# ReadyUNO_SMD.net
KiCad netlist of a schematic drawn in EAGLE
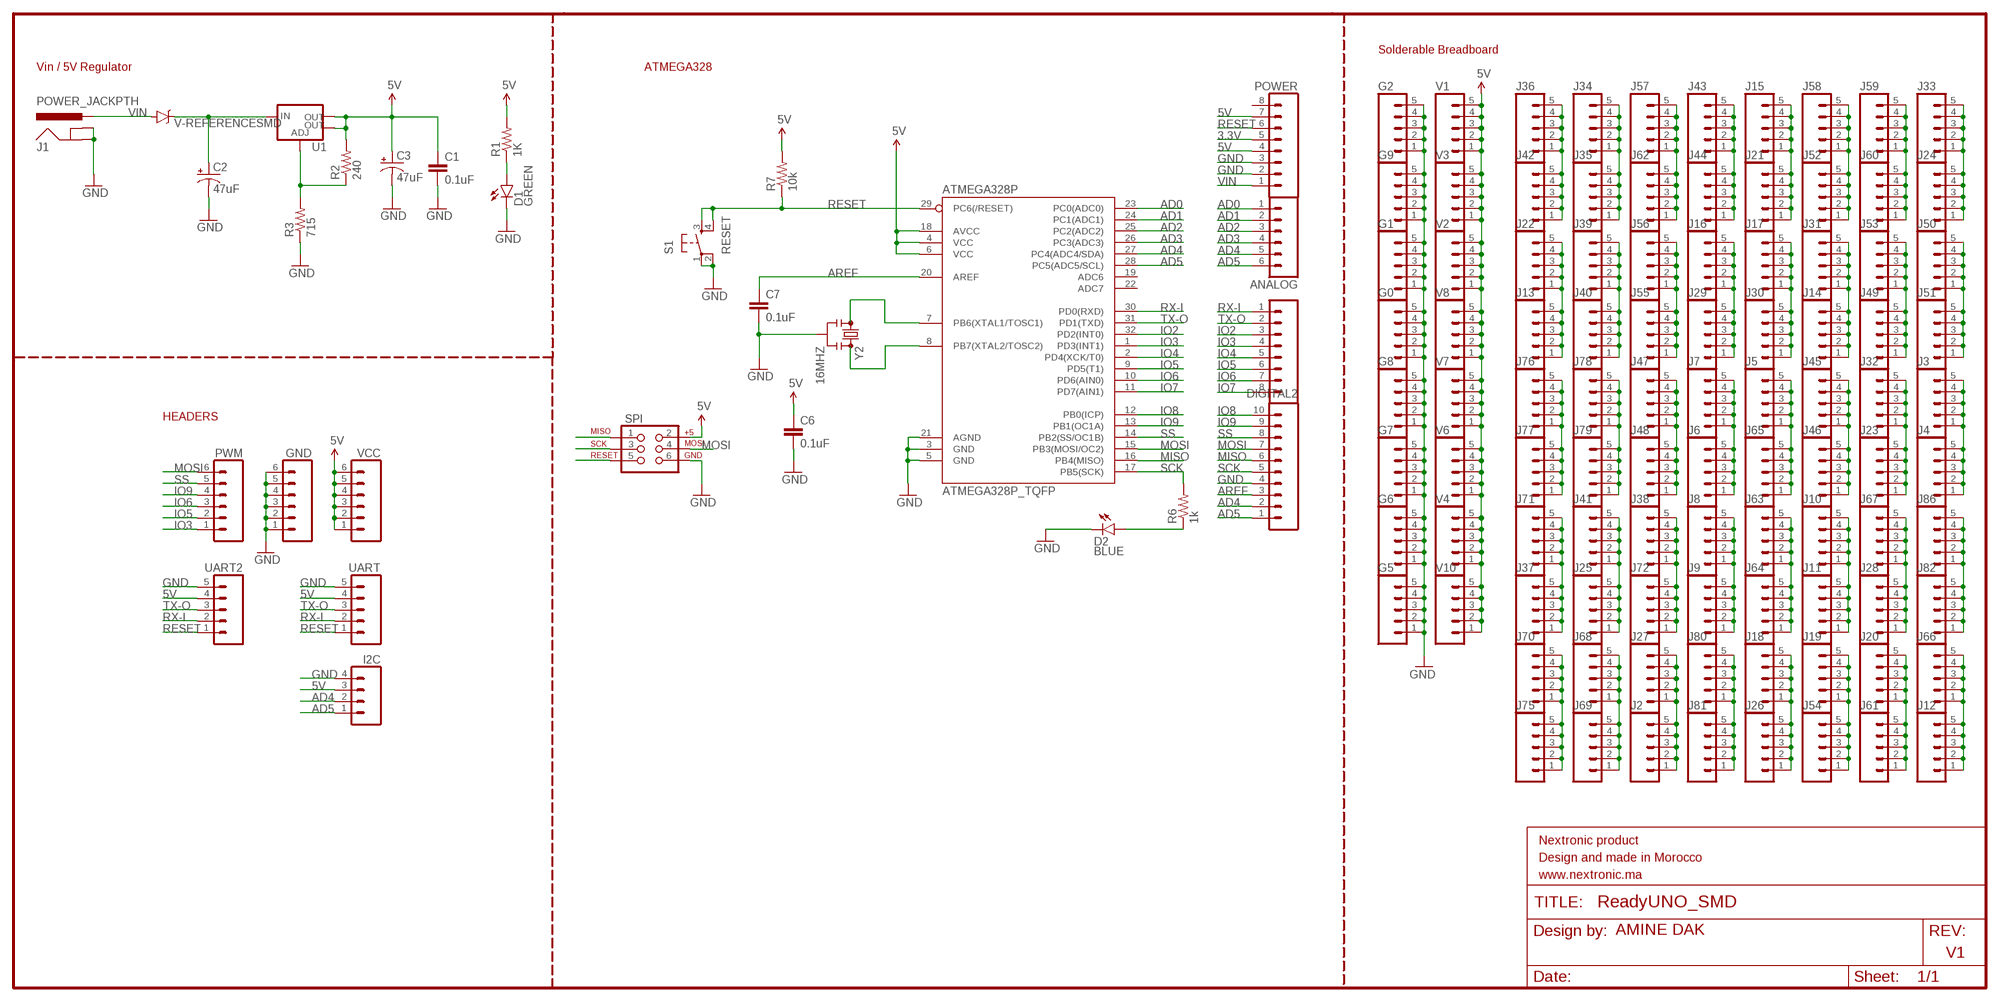
[diagram p0: schematic, sheet 1]

(export (version "E")
  (design (tool "Eeschema 10.0.6"))
  (components
    (comp (ref "ANALOG")
      (value "M06SILK_FEMALE_PTH")
      (footprint "eagle-import:1X06")
      (libsource (lib "eagle-import") (part "M06SILK_FEMALE_PTH"))
    )
    (comp (ref "ATMEGA328P")
      (value "ATMEGA328P_TQFP")
      (footprint "eagle-import:TQFP32-08")
      (libsource (lib "eagle-import") (part "ATMEGA328P_TQFP"))
    )
    (comp (ref "C1")
      (value "0.1uF")
      (footprint "eagle-import:0603-CAP")
      (libsource (lib "eagle-import") (part "CAP0603-CAP"))
    )
    (comp (ref "C2")
      (value "47uF")
      (footprint "eagle-import:PANASONIC_C")
      (libsource (lib "eagle-import") (part "CAP_POLC"))
    )
    (comp (ref "C3")
      (value "47uF")
      (footprint "eagle-import:PANASONIC_C")
      (libsource (lib "eagle-import") (part "CAP_POLC"))
    )
    (comp (ref "C6")
      (value "0.1uF")
      (footprint "eagle-import:0603-CAP")
      (libsource (lib "eagle-import") (part "CAP0603-CAP"))
    )
    (comp (ref "C7")
      (value "0.1uF")
      (footprint "eagle-import:0603-CAP")
      (libsource (lib "eagle-import") (part "CAP0603-CAP"))
    )
    (comp (ref "D1")
      (value "GREEN")
      (footprint "eagle-import:LED-1206")
      (libsource (lib "eagle-import") (part "LED-GREEN1206"))
    )
    (comp (ref "D2")
      (value "BLUE")
      (footprint "eagle-import:LED-1206")
      (libsource (lib "eagle-import") (part "LED-BLUE1206"))
    )
    (comp (ref "DIGITAL")
      (value "M08SILK_FEMALE_PTH")
      (footprint "eagle-import:1X08")
      (libsource (lib "eagle-import") (part "M08SILK_FEMALE_PTH"))
    )
    (comp (ref "DIGITAL2")
      (value "M10SILK_FEMALE_PTH")
      (footprint "eagle-import:1X10")
      (libsource (lib "eagle-import") (part "M10SILK_FEMALE_PTH"))
    )
    (comp (ref "FRAME1")
      (value "FRAME-LETTER")
      (footprint "eagle-import:CREATIVE_COMMONS")
      (libsource (lib "eagle-import") (part "FRAME-LETTER"))
    )
    (comp (ref "G0")
      (value "M05PTH")
      (footprint "eagle-import:1X05")
      (libsource (lib "eagle-import") (part "M05PTH"))
    )
    (comp (ref "G1")
      (value "M05PTH")
      (footprint "eagle-import:1X05")
      (libsource (lib "eagle-import") (part "M05PTH"))
    )
    (comp (ref "G2")
      (value "M05PTH")
      (footprint "eagle-import:1X05")
      (libsource (lib "eagle-import") (part "M05PTH"))
    )
    (comp (ref "G5")
      (value "M05PTH")
      (footprint "eagle-import:1X05")
      (libsource (lib "eagle-import") (part "M05PTH"))
    )
    (comp (ref "G6")
      (value "M05PTH")
      (footprint "eagle-import:1X05")
      (libsource (lib "eagle-import") (part "M05PTH"))
    )
    (comp (ref "G7")
      (value "M05PTH")
      (footprint "eagle-import:1X05")
      (libsource (lib "eagle-import") (part "M05PTH"))
    )
    (comp (ref "G8")
      (value "M05PTH")
      (footprint "eagle-import:1X05")
      (libsource (lib "eagle-import") (part "M05PTH"))
    )
    (comp (ref "G9")
      (value "M05PTH")
      (footprint "eagle-import:1X05")
      (libsource (lib "eagle-import") (part "M05PTH"))
    )
    (comp (ref "GND")
      (value "M06SILK_FEMALE_PTH")
      (footprint "eagle-import:1X06")
      (libsource (lib "eagle-import") (part "M06SILK_FEMALE_PTH"))
    )
    (comp (ref "I2C")
      (value "M04PTH")
      (footprint "eagle-import:1X04")
      (libsource (lib "eagle-import") (part "M04PTH"))
    )
    (comp (ref "J1")
      (value "POWER_JACKPTH")
      (footprint "eagle-import:POWER_JACK_PTH")
      (libsource (lib "eagle-import") (part "POWER_JACKPTH"))
    )
    (comp (ref "J2")
      (value "M05PTH")
      (footprint "eagle-import:1X05")
      (libsource (lib "eagle-import") (part "M05PTH"))
    )
    (comp (ref "J3")
      (value "M05PTH")
      (footprint "eagle-import:1X05")
      (libsource (lib "eagle-import") (part "M05PTH"))
    )
    (comp (ref "J4")
      (value "M05PTH")
      (footprint "eagle-import:1X05")
      (libsource (lib "eagle-import") (part "M05PTH"))
    )
    (comp (ref "J5")
      (value "M05PTH")
      (footprint "eagle-import:1X05")
      (libsource (lib "eagle-import") (part "M05PTH"))
    )
    (comp (ref "J6")
      (value "M05PTH")
      (footprint "eagle-import:1X05")
      (libsource (lib "eagle-import") (part "M05PTH"))
    )
    (comp (ref "J7")
      (value "M05PTH")
      (footprint "eagle-import:1X05")
      (libsource (lib "eagle-import") (part "M05PTH"))
    )
    (comp (ref "J8")
      (value "M05PTH")
      (footprint "eagle-import:1X05")
      (libsource (lib "eagle-import") (part "M05PTH"))
    )
    (comp (ref "J9")
      (value "M05PTH")
      (footprint "eagle-import:1X05")
      (libsource (lib "eagle-import") (part "M05PTH"))
    )
    (comp (ref "J10")
      (value "M05PTH")
      (footprint "eagle-import:1X05")
      (libsource (lib "eagle-import") (part "M05PTH"))
    )
    (comp (ref "J11")
      (value "M05PTH")
      (footprint "eagle-import:1X05")
      (libsource (lib "eagle-import") (part "M05PTH"))
    )
    (comp (ref "J12")
      (value "M05PTH")
      (footprint "eagle-import:1X05")
      (libsource (lib "eagle-import") (part "M05PTH"))
    )
    (comp (ref "J13")
      (value "M05PTH")
      (footprint "eagle-import:1X05")
      (libsource (lib "eagle-import") (part "M05PTH"))
    )
    (comp (ref "J14")
      (value "M05PTH")
      (footprint "eagle-import:1X05")
      (libsource (lib "eagle-import") (part "M05PTH"))
    )
    (comp (ref "J15")
      (value "M05PTH")
      (footprint "eagle-import:1X05")
      (libsource (lib "eagle-import") (part "M05PTH"))
    )
    (comp (ref "J16")
      (value "M05PTH")
      (footprint "eagle-import:1X05")
      (libsource (lib "eagle-import") (part "M05PTH"))
    )
    (comp (ref "J17")
      (value "M05PTH")
      (footprint "eagle-import:1X05")
      (libsource (lib "eagle-import") (part "M05PTH"))
    )
    (comp (ref "J18")
      (value "M05PTH")
      (footprint "eagle-import:1X05")
      (libsource (lib "eagle-import") (part "M05PTH"))
    )
    (comp (ref "J19")
      (value "M05PTH")
      (footprint "eagle-import:1X05")
      (libsource (lib "eagle-import") (part "M05PTH"))
    )
    (comp (ref "J20")
      (value "M05PTH")
      (footprint "eagle-import:1X05")
      (libsource (lib "eagle-import") (part "M05PTH"))
    )
    (comp (ref "J21")
      (value "M05PTH")
      (footprint "eagle-import:1X05")
      (libsource (lib "eagle-import") (part "M05PTH"))
    )
    (comp (ref "J22")
      (value "M05PTH")
      (footprint "eagle-import:1X05")
      (libsource (lib "eagle-import") (part "M05PTH"))
    )
    (comp (ref "J23")
      (value "M05PTH")
      (footprint "eagle-import:1X05")
      (libsource (lib "eagle-import") (part "M05PTH"))
    )
    (comp (ref "J24")
      (value "M05PTH")
      (footprint "eagle-import:1X05")
      (libsource (lib "eagle-import") (part "M05PTH"))
    )
    (comp (ref "J25")
      (value "M05PTH")
      (footprint "eagle-import:1X05")
      (libsource (lib "eagle-import") (part "M05PTH"))
    )
    (comp (ref "J26")
      (value "M05PTH")
      (footprint "eagle-import:1X05")
      (libsource (lib "eagle-import") (part "M05PTH"))
    )
    (comp (ref "J27")
      (value "M05PTH")
      (footprint "eagle-import:1X05")
      (libsource (lib "eagle-import") (part "M05PTH"))
    )
    (comp (ref "J28")
      (value "M05PTH")
      (footprint "eagle-import:1X05")
      (libsource (lib "eagle-import") (part "M05PTH"))
    )
    (comp (ref "J29")
      (value "M05PTH")
      (footprint "eagle-import:1X05")
      (libsource (lib "eagle-import") (part "M05PTH"))
    )
    (comp (ref "J30")
      (value "M05PTH")
      (footprint "eagle-import:1X05")
      (libsource (lib "eagle-import") (part "M05PTH"))
    )
    (comp (ref "J31")
      (value "M05PTH")
      (footprint "eagle-import:1X05")
      (libsource (lib "eagle-import") (part "M05PTH"))
    )
    (comp (ref "J32")
      (value "M05PTH")
      (footprint "eagle-import:1X05")
      (libsource (lib "eagle-import") (part "M05PTH"))
    )
    (comp (ref "J33")
      (value "M05PTH")
      (footprint "eagle-import:1X05")
      (libsource (lib "eagle-import") (part "M05PTH"))
    )
    (comp (ref "J34")
      (value "M05PTH")
      (footprint "eagle-import:1X05")
      (libsource (lib "eagle-import") (part "M05PTH"))
    )
    (comp (ref "J35")
      (value "M05PTH")
      (footprint "eagle-import:1X05")
      (libsource (lib "eagle-import") (part "M05PTH"))
    )
    (comp (ref "J36")
      (value "M05PTH")
      (footprint "eagle-import:1X05")
      (libsource (lib "eagle-import") (part "M05PTH"))
    )
    (comp (ref "J37")
      (value "M05PTH")
      (footprint "eagle-import:1X05")
      (libsource (lib "eagle-import") (part "M05PTH"))
    )
    (comp (ref "J38")
      (value "M05PTH")
      (footprint "eagle-import:1X05")
      (libsource (lib "eagle-import") (part "M05PTH"))
    )
    (comp (ref "J39")
      (value "M05PTH")
      (footprint "eagle-import:1X05")
      (libsource (lib "eagle-import") (part "M05PTH"))
    )
    (comp (ref "J40")
      (value "M05PTH")
      (footprint "eagle-import:1X05")
      (libsource (lib "eagle-import") (part "M05PTH"))
    )
    (comp (ref "J41")
      (value "M05PTH")
      (footprint "eagle-import:1X05")
      (libsource (lib "eagle-import") (part "M05PTH"))
    )
    (comp (ref "J42")
      (value "M05PTH")
      (footprint "eagle-import:1X05")
      (libsource (lib "eagle-import") (part "M05PTH"))
    )
    (comp (ref "J43")
      (value "M05PTH")
      (footprint "eagle-import:1X05")
      (libsource (lib "eagle-import") (part "M05PTH"))
    )
    (comp (ref "J44")
      (value "M05PTH")
      (footprint "eagle-import:1X05")
      (libsource (lib "eagle-import") (part "M05PTH"))
    )
    (comp (ref "J45")
      (value "M05PTH")
      (footprint "eagle-import:1X05")
      (libsource (lib "eagle-import") (part "M05PTH"))
    )
    (comp (ref "J46")
      (value "M05PTH")
      (footprint "eagle-import:1X05")
      (libsource (lib "eagle-import") (part "M05PTH"))
    )
    (comp (ref "J47")
      (value "M05PTH")
      (footprint "eagle-import:1X05")
      (libsource (lib "eagle-import") (part "M05PTH"))
    )
    (comp (ref "J48")
      (value "M05PTH")
      (footprint "eagle-import:1X05")
      (libsource (lib "eagle-import") (part "M05PTH"))
    )
    (comp (ref "J49")
      (value "M05PTH")
      (footprint "eagle-import:1X05")
      (libsource (lib "eagle-import") (part "M05PTH"))
    )
    (comp (ref "J50")
      (value "M05PTH")
      (footprint "eagle-import:1X05")
      (libsource (lib "eagle-import") (part "M05PTH"))
    )
    (comp (ref "J51")
      (value "M05PTH")
      (footprint "eagle-import:1X05")
      (libsource (lib "eagle-import") (part "M05PTH"))
    )
    (comp (ref "J52")
      (value "M05PTH")
      (footprint "eagle-import:1X05")
      (libsource (lib "eagle-import") (part "M05PTH"))
    )
    (comp (ref "J53")
      (value "M05PTH")
      (footprint "eagle-import:1X05")
      (libsource (lib "eagle-import") (part "M05PTH"))
    )
    (comp (ref "J54")
      (value "M05PTH")
      (footprint "eagle-import:1X05")
      (libsource (lib "eagle-import") (part "M05PTH"))
    )
    (comp (ref "J55")
      (value "M05PTH")
      (footprint "eagle-import:1X05")
      (libsource (lib "eagle-import") (part "M05PTH"))
    )
    (comp (ref "J56")
      (value "M05PTH")
      (footprint "eagle-import:1X05")
      (libsource (lib "eagle-import") (part "M05PTH"))
    )
    (comp (ref "J57")
      (value "M05PTH")
      (footprint "eagle-import:1X05")
      (libsource (lib "eagle-import") (part "M05PTH"))
    )
    (comp (ref "J58")
      (value "M05PTH")
      (footprint "eagle-import:1X05")
      (libsource (lib "eagle-import") (part "M05PTH"))
    )
    (comp (ref "J59")
      (value "M05PTH")
      (footprint "eagle-import:1X05")
      (libsource (lib "eagle-import") (part "M05PTH"))
    )
    (comp (ref "J60")
      (value "M05PTH")
      (footprint "eagle-import:1X05")
      (libsource (lib "eagle-import") (part "M05PTH"))
    )
    (comp (ref "J61")
      (value "M05PTH")
      (footprint "eagle-import:1X05")
      (libsource (lib "eagle-import") (part "M05PTH"))
    )
    (comp (ref "J62")
      (value "M05PTH")
      (footprint "eagle-import:1X05")
      (libsource (lib "eagle-import") (part "M05PTH"))
    )
    (comp (ref "J63")
      (value "M05PTH")
      (footprint "eagle-import:1X05")
      (libsource (lib "eagle-import") (part "M05PTH"))
    )
    (comp (ref "J64")
      (value "M05PTH")
      (footprint "eagle-import:1X05")
      (libsource (lib "eagle-import") (part "M05PTH"))
    )
    (comp (ref "J65")
      (value "M05PTH")
      (footprint "eagle-import:1X05")
      (libsource (lib "eagle-import") (part "M05PTH"))
    )
    (comp (ref "J66")
      (value "M05PTH")
      (footprint "eagle-import:1X05")
      (libsource (lib "eagle-import") (part "M05PTH"))
    )
    (comp (ref "J67")
      (value "M05PTH")
      (footprint "eagle-import:1X05")
      (libsource (lib "eagle-import") (part "M05PTH"))
    )
    (comp (ref "J68")
      (value "M05PTH")
      (footprint "eagle-import:1X05")
      (libsource (lib "eagle-import") (part "M05PTH"))
    )
    (comp (ref "J69")
      (value "M05PTH")
      (footprint "eagle-import:1X05")
      (libsource (lib "eagle-import") (part "M05PTH"))
    )
    (comp (ref "J70")
      (value "M05PTH")
      (footprint "eagle-import:1X05")
      (libsource (lib "eagle-import") (part "M05PTH"))
    )
    (comp (ref "J71")
      (value "M05PTH")
      (footprint "eagle-import:1X05")
      (libsource (lib "eagle-import") (part "M05PTH"))
    )
    (comp (ref "J72")
      (value "M05PTH")
      (footprint "eagle-import:1X05")
      (libsource (lib "eagle-import") (part "M05PTH"))
    )
    (comp (ref "J75")
      (value "M05PTH")
      (footprint "eagle-import:1X05")
      (libsource (lib "eagle-import") (part "M05PTH"))
    )
    (comp (ref "J76")
      (value "M05PTH")
      (footprint "eagle-import:1X05")
      (libsource (lib "eagle-import") (part "M05PTH"))
    )
    (comp (ref "J77")
      (value "M05PTH")
      (footprint "eagle-import:1X05")
      (libsource (lib "eagle-import") (part "M05PTH"))
    )
    (comp (ref "J78")
      (value "M05PTH")
      (footprint "eagle-import:1X05")
      (libsource (lib "eagle-import") (part "M05PTH"))
    )
    (comp (ref "J79")
      (value "M05PTH")
      (footprint "eagle-import:1X05")
      (libsource (lib "eagle-import") (part "M05PTH"))
    )
    (comp (ref "J80")
      (value "M05PTH")
      (footprint "eagle-import:1X05")
      (libsource (lib "eagle-import") (part "M05PTH"))
    )
    (comp (ref "J81")
      (value "M05PTH")
      (footprint "eagle-import:1X05")
      (libsource (lib "eagle-import") (part "M05PTH"))
    )
    (comp (ref "J82")
      (value "M05PTH")
      (footprint "eagle-import:1X05")
      (libsource (lib "eagle-import") (part "M05PTH"))
    )
    (comp (ref "J86")
      (value "M05PTH")
      (footprint "eagle-import:1X05")
      (libsource (lib "eagle-import") (part "M05PTH"))
    )
    (comp (ref "POWER")
      (value "M08SILK_FEMALE_PTH")
      (footprint "eagle-import:1X08")
      (libsource (lib "eagle-import") (part "M08SILK_FEMALE_PTH"))
    )
    (comp (ref "PWM")
      (value "M06SILK_FEMALE_PTH")
      (footprint "eagle-import:1X06")
      (libsource (lib "eagle-import") (part "M06SILK_FEMALE_PTH"))
    )
    (comp (ref "R1")
      (value "1K")
      (footprint "eagle-import:0603-RES")
      (libsource (lib "eagle-import") (part "RESISTOR0603-RES"))
    )
    (comp (ref "R2")
      (value "240")
      (footprint "eagle-import:0603-RES")
      (libsource (lib "eagle-import") (part "RESISTOR0603-RES"))
    )
    (comp (ref "R3")
      (value "715")
      (footprint "eagle-import:0603-RES")
      (libsource (lib "eagle-import") (part "RESISTOR0603-RES"))
    )
    (comp (ref "R6")
      (value "1k")
      (footprint "eagle-import:0603-RES")
      (libsource (lib "eagle-import") (part "RESISTOR0603-RES"))
    )
    (comp (ref "R7")
      (value "10k")
      (footprint "eagle-import:0603-RES")
      (libsource (lib "eagle-import") (part "RESISTOR0603-RES"))
    )
    (comp (ref "S1")
      (value "RESET")
      (footprint "eagle-import:TACTILE-SWITCH-SMD")
      (libsource (lib "eagle-import") (part "TAC_SWITCHSMD"))
    )
    (comp (ref "SPI")
      (value "AVR_SPI_PRG_6NS")
      (footprint "eagle-import:2X3-NS")
      (libsource (lib "eagle-import") (part "AVR_SPI_PRG_6NS"))
    )
    (comp (ref "U$1")
      (value "V-REFERENCESMD")
      (footprint "eagle-import:SOT23-3")
      (libsource (lib "eagle-import") (part "V-REFERENCESMD"))
    )
    (comp (ref "U1")
      (value "V_REG_LM1117SOT223")
      (footprint "eagle-import:SOT223")
      (libsource (lib "eagle-import") (part "V_REG_LM1117SOT223"))
    )
    (comp (ref "UART")
      (value "M05PTH")
      (footprint "eagle-import:1X05")
      (libsource (lib "eagle-import") (part "M05PTH"))
    )
    (comp (ref "UART2")
      (value "M05PTH")
      (footprint "eagle-import:1X05")
      (libsource (lib "eagle-import") (part "M05PTH"))
    )
    (comp (ref "V1")
      (value "M05PTH")
      (footprint "eagle-import:1X05")
      (libsource (lib "eagle-import") (part "M05PTH"))
    )
    (comp (ref "V2")
      (value "M05PTH")
      (footprint "eagle-import:1X05")
      (libsource (lib "eagle-import") (part "M05PTH"))
    )
    (comp (ref "V3")
      (value "M05PTH")
      (footprint "eagle-import:1X05")
      (libsource (lib "eagle-import") (part "M05PTH"))
    )
    (comp (ref "V4")
      (value "M05PTH")
      (footprint "eagle-import:1X05")
      (libsource (lib "eagle-import") (part "M05PTH"))
    )
    (comp (ref "V6")
      (value "M05PTH")
      (footprint "eagle-import:1X05")
      (libsource (lib "eagle-import") (part "M05PTH"))
    )
    (comp (ref "V7")
      (value "M05PTH")
      (footprint "eagle-import:1X05")
      (libsource (lib "eagle-import") (part "M05PTH"))
    )
    (comp (ref "V8")
      (value "M05PTH")
      (footprint "eagle-import:1X05")
      (libsource (lib "eagle-import") (part "M05PTH"))
    )
    (comp (ref "V10")
      (value "M05PTH")
      (footprint "eagle-import:1X05")
      (libsource (lib "eagle-import") (part "M05PTH"))
    )
    (comp (ref "VCC")
      (value "M06SILK_FEMALE_PTH")
      (footprint "eagle-import:1X06")
      (libsource (lib "eagle-import") (part "M06SILK_FEMALE_PTH"))
    )
    (comp (ref "Y2")
      (value "16MHZ")
      (footprint "eagle-import:RESONATOR-SMD")
      (libsource (lib "eagle-import") (part "RESONATOR16MHZ"))
    )
  )
  (nets
    (net (code "1") (name "/3.3V") (class "Default")
      (node (ref "POWER") (pin "5") (pinfunction "5_5") (pintype "passive"))
    )
    (net (code "2") (name "/AD0") (class "Default")
      (node (ref "ANALOG") (pin "1") (pinfunction "1_1") (pintype "passive"))
      (node (ref "ATMEGA328P") (pin "23") (pinfunction "PC0(ADC0)_23") (pintype "bidirectional"))
    )
    (net (code "3") (name "/AD1") (class "Default")
      (node (ref "ANALOG") (pin "2") (pinfunction "2_2") (pintype "passive"))
      (node (ref "ATMEGA328P") (pin "24") (pinfunction "PC1(ADC1)_24") (pintype "bidirectional"))
    )
    (net (code "4") (name "/AD2") (class "Default")
      (node (ref "ANALOG") (pin "3") (pinfunction "3_3") (pintype "passive"))
      (node (ref "ATMEGA328P") (pin "25") (pinfunction "PC2(ADC2)_25") (pintype "bidirectional"))
    )
    (net (code "5") (name "/AD3") (class "Default")
      (node (ref "ANALOG") (pin "4") (pinfunction "4_4") (pintype "passive"))
      (node (ref "ATMEGA328P") (pin "26") (pinfunction "PC3(ADC3)_26") (pintype "bidirectional"))
    )
    (net (code "6") (name "/AD4") (class "Default")
      (node (ref "ANALOG") (pin "5") (pinfunction "5_5") (pintype "passive"))
      (node (ref "ATMEGA328P") (pin "27") (pinfunction "PC4(ADC4/SDA)_27") (pintype "bidirectional"))
      (node (ref "DIGITAL2") (pin "2") (pinfunction "2_2") (pintype "passive"))
      (node (ref "I2C") (pin "2") (pinfunction "2_2") (pintype "passive"))
    )
    (net (code "7") (name "/AD5") (class "Default")
      (node (ref "ANALOG") (pin "6") (pinfunction "6_6") (pintype "passive"))
      (node (ref "ATMEGA328P") (pin "28") (pinfunction "PC5(ADC5/SCL)_28") (pintype "bidirectional"))
      (node (ref "DIGITAL2") (pin "1") (pinfunction "1_1") (pintype "passive"))
      (node (ref "I2C") (pin "1") (pinfunction "1_1") (pintype "passive"))
    )
    (net (code "8") (name "/AREF") (class "Default")
      (node (ref "ATMEGA328P") (pin "20") (pinfunction "AREF_20") (pintype "bidirectional"))
      (node (ref "C7") (pin "1") (pinfunction "1_1") (pintype "passive"))
      (node (ref "DIGITAL2") (pin "3") (pinfunction "3_3") (pintype "passive"))
    )
    (net (code "9") (name "/IO2") (class "Default")
      (node (ref "ATMEGA328P") (pin "32") (pinfunction "PD2(INT0)_32") (pintype "bidirectional"))
      (node (ref "DIGITAL") (pin "3") (pinfunction "3_3") (pintype "passive"))
    )
    (net (code "10") (name "/IO3") (class "Default")
      (node (ref "ATMEGA328P") (pin "1") (pinfunction "PD3(INT1)_1") (pintype "bidirectional"))
      (node (ref "DIGITAL") (pin "4") (pinfunction "4_4") (pintype "passive"))
      (node (ref "PWM") (pin "1") (pinfunction "1_1") (pintype "passive"))
    )
    (net (code "11") (name "/IO4") (class "Default")
      (node (ref "ATMEGA328P") (pin "2") (pinfunction "PD4(XCK/T0)_2") (pintype "bidirectional"))
      (node (ref "DIGITAL") (pin "5") (pinfunction "5_5") (pintype "passive"))
    )
    (net (code "12") (name "/IO5") (class "Default")
      (node (ref "ATMEGA328P") (pin "9") (pinfunction "PD5(T1)_9") (pintype "bidirectional"))
      (node (ref "DIGITAL") (pin "6") (pinfunction "6_6") (pintype "passive"))
      (node (ref "PWM") (pin "2") (pinfunction "2_2") (pintype "passive"))
    )
    (net (code "13") (name "/IO6") (class "Default")
      (node (ref "ATMEGA328P") (pin "10") (pinfunction "PD6(AIN0)_10") (pintype "bidirectional"))
      (node (ref "DIGITAL") (pin "7") (pinfunction "7_7") (pintype "passive"))
      (node (ref "PWM") (pin "3") (pinfunction "3_3") (pintype "passive"))
    )
    (net (code "14") (name "/IO7") (class "Default")
      (node (ref "ATMEGA328P") (pin "11") (pinfunction "PD7(AIN1)_11") (pintype "bidirectional"))
      (node (ref "DIGITAL") (pin "8") (pinfunction "8_8") (pintype "passive"))
    )
    (net (code "15") (name "/IO8") (class "Default")
      (node (ref "ATMEGA328P") (pin "12") (pinfunction "PB0(ICP)_12") (pintype "bidirectional"))
      (node (ref "DIGITAL2") (pin "10") (pinfunction "10_10") (pintype "passive"))
    )
    (net (code "16") (name "/IO9") (class "Default")
      (node (ref "ATMEGA328P") (pin "13") (pinfunction "PB1(OC1A)_13") (pintype "bidirectional"))
      (node (ref "DIGITAL2") (pin "9") (pinfunction "9_9") (pintype "passive"))
      (node (ref "PWM") (pin "4") (pinfunction "4_4") (pintype "passive"))
    )
    (net (code "17") (name "/MISO") (class "Default")
      (node (ref "ATMEGA328P") (pin "16") (pinfunction "PB4(MISO)_16") (pintype "bidirectional"))
      (node (ref "DIGITAL2") (pin "6") (pinfunction "6_6") (pintype "passive"))
      (node (ref "SPI") (pin "1") (pinfunction "1_1") (pintype "passive"))
    )
    (net (code "18") (name "/MOSI") (class "Default")
      (node (ref "ATMEGA328P") (pin "15") (pinfunction "PB3(MOSI/OC2)_15") (pintype "bidirectional"))
      (node (ref "DIGITAL2") (pin "7") (pinfunction "7_7") (pintype "passive"))
      (node (ref "PWM") (pin "6") (pinfunction "6_6") (pintype "passive"))
      (node (ref "SPI") (pin "4") (pinfunction "4_4") (pintype "passive"))
    )
    (net (code "19") (name "/RESET") (class "Default")
      (node (ref "ATMEGA328P") (pin "29") (pinfunction "PC6(/RESET)_29") (pintype "bidirectional"))
      (node (ref "POWER") (pin "6") (pinfunction "6_6") (pintype "passive"))
      (node (ref "R7") (pin "1") (pinfunction "1_1") (pintype "passive"))
      (node (ref "S1") (pin "3") (pinfunction "3_3") (pintype "passive"))
      (node (ref "S1") (pin "4") (pinfunction "4_4") (pintype "passive"))
      (node (ref "SPI") (pin "5") (pinfunction "5_5") (pintype "passive"))
      (node (ref "UART") (pin "1") (pinfunction "1_1") (pintype "passive"))
      (node (ref "UART2") (pin "1") (pinfunction "1_1") (pintype "passive"))
    )
    (net (code "20") (name "/RX-I") (class "Default")
      (node (ref "ATMEGA328P") (pin "30") (pinfunction "PD0(RXD)_30") (pintype "bidirectional"))
      (node (ref "DIGITAL") (pin "1") (pinfunction "1_1") (pintype "passive"))
      (node (ref "UART") (pin "2") (pinfunction "2_2") (pintype "passive"))
      (node (ref "UART2") (pin "2") (pinfunction "2_2") (pintype "passive"))
    )
    (net (code "21") (name "/SCK") (class "Default")
      (node (ref "ATMEGA328P") (pin "17") (pinfunction "PB5(SCK)_17") (pintype "bidirectional"))
      (node (ref "DIGITAL2") (pin "5") (pinfunction "5_5") (pintype "passive"))
      (node (ref "R6") (pin "2") (pinfunction "2_2") (pintype "passive"))
      (node (ref "SPI") (pin "3") (pinfunction "3_3") (pintype "passive"))
    )
    (net (code "22") (name "/SS") (class "Default")
      (node (ref "ATMEGA328P") (pin "14") (pinfunction "PB2(SS/OC1B)_14") (pintype "bidirectional"))
      (node (ref "DIGITAL2") (pin "8") (pinfunction "8_8") (pintype "passive"))
      (node (ref "PWM") (pin "5") (pinfunction "5_5") (pintype "passive"))
    )
    (net (code "23") (name "/TX-O") (class "Default")
      (node (ref "ATMEGA328P") (pin "31") (pinfunction "PD1(TXD)_31") (pintype "bidirectional"))
      (node (ref "DIGITAL") (pin "2") (pinfunction "2_2") (pintype "passive"))
      (node (ref "UART") (pin "3") (pinfunction "3_3") (pintype "passive"))
      (node (ref "UART2") (pin "3") (pinfunction "3_3") (pintype "passive"))
    )
    (net (code "24") (name "/VIN") (class "Default")
      (node (ref "J1") (pin "PWR") (pinfunction "PWR_PWR") (pintype "bidirectional"))
      (node (ref "POWER") (pin "1") (pinfunction "1_1") (pintype "passive"))
      (node (ref "U$1") (pin "2") (pinfunction "A_2") (pintype "passive"))
    )
    (net (code "25") (name "5V") (class "Default")
      (node (ref "ATMEGA328P") (pin "18") (pinfunction "AVCC_18") (pintype "bidirectional"))
      (node (ref "ATMEGA328P") (pin "4") (pinfunction "VCC_4") (pintype "bidirectional"))
      (node (ref "ATMEGA328P") (pin "6") (pinfunction "VCC_6") (pintype "bidirectional"))
      (node (ref "C1") (pin "1") (pinfunction "1_1") (pintype "passive"))
      (node (ref "C3") (pin "+") (pinfunction "+_+") (pintype "passive"))
      (node (ref "C6") (pin "1") (pinfunction "1_1") (pintype "passive"))
      (node (ref "I2C") (pin "3") (pinfunction "3_3") (pintype "passive"))
      (node (ref "POWER") (pin "4") (pinfunction "4_4") (pintype "passive"))
      (node (ref "POWER") (pin "7") (pinfunction "7_7") (pintype "passive"))
      (node (ref "R1") (pin "2") (pinfunction "2_2") (pintype "passive"))
      (node (ref "R2") (pin "2") (pinfunction "2_2") (pintype "passive"))
      (node (ref "R7") (pin "2") (pinfunction "2_2") (pintype "passive"))
      (node (ref "SPI") (pin "2") (pinfunction "2_2") (pintype "passive"))
      (node (ref "U1") (pin "2") (pinfunction "OUT_2") (pintype "output"))
      (node (ref "U1") (pin "4") (pinfunction "OUT_4") (pintype "output"))
      (node (ref "UART") (pin "4") (pinfunction "4_4") (pintype "passive"))
      (node (ref "UART2") (pin "4") (pinfunction "4_4") (pintype "passive"))
      (node (ref "V1") (pin "1") (pinfunction "1_1") (pintype "passive"))
      (node (ref "V1") (pin "2") (pinfunction "2_2") (pintype "passive"))
      (node (ref "V1") (pin "3") (pinfunction "3_3") (pintype "passive"))
      (node (ref "V1") (pin "4") (pinfunction "4_4") (pintype "passive"))
      (node (ref "V1") (pin "5") (pinfunction "5_5") (pintype "passive"))
      (node (ref "V10") (pin "1") (pinfunction "1_1") (pintype "passive"))
      (node (ref "V10") (pin "2") (pinfunction "2_2") (pintype "passive"))
      (node (ref "V10") (pin "3") (pinfunction "3_3") (pintype "passive"))
      (node (ref "V10") (pin "4") (pinfunction "4_4") (pintype "passive"))
      (node (ref "V10") (pin "5") (pinfunction "5_5") (pintype "passive"))
      (node (ref "V2") (pin "1") (pinfunction "1_1") (pintype "passive"))
      (node (ref "V2") (pin "2") (pinfunction "2_2") (pintype "passive"))
      (node (ref "V2") (pin "3") (pinfunction "3_3") (pintype "passive"))
      (node (ref "V2") (pin "4") (pinfunction "4_4") (pintype "passive"))
      (node (ref "V2") (pin "5") (pinfunction "5_5") (pintype "passive"))
      (node (ref "V3") (pin "1") (pinfunction "1_1") (pintype "passive"))
      (node (ref "V3") (pin "2") (pinfunction "2_2") (pintype "passive"))
      (node (ref "V3") (pin "3") (pinfunction "3_3") (pintype "passive"))
      (node (ref "V3") (pin "4") (pinfunction "4_4") (pintype "passive"))
      (node (ref "V3") (pin "5") (pinfunction "5_5") (pintype "passive"))
      (node (ref "V4") (pin "1") (pinfunction "1_1") (pintype "passive"))
      (node (ref "V4") (pin "2") (pinfunction "2_2") (pintype "passive"))
      (node (ref "V4") (pin "3") (pinfunction "3_3") (pintype "passive"))
      (node (ref "V4") (pin "4") (pinfunction "4_4") (pintype "passive"))
      (node (ref "V4") (pin "5") (pinfunction "5_5") (pintype "passive"))
      (node (ref "V6") (pin "1") (pinfunction "1_1") (pintype "passive"))
      (node (ref "V6") (pin "2") (pinfunction "2_2") (pintype "passive"))
      (node (ref "V6") (pin "3") (pinfunction "3_3") (pintype "passive"))
      (node (ref "V6") (pin "4") (pinfunction "4_4") (pintype "passive"))
      (node (ref "V6") (pin "5") (pinfunction "5_5") (pintype "passive"))
      (node (ref "V7") (pin "1") (pinfunction "1_1") (pintype "passive"))
      (node (ref "V7") (pin "2") (pinfunction "2_2") (pintype "passive"))
      (node (ref "V7") (pin "3") (pinfunction "3_3") (pintype "passive"))
      (node (ref "V7") (pin "4") (pinfunction "4_4") (pintype "passive"))
      (node (ref "V7") (pin "5") (pinfunction "5_5") (pintype "passive"))
      (node (ref "V8") (pin "1") (pinfunction "1_1") (pintype "passive"))
      (node (ref "V8") (pin "2") (pinfunction "2_2") (pintype "passive"))
      (node (ref "V8") (pin "3") (pinfunction "3_3") (pintype "passive"))
      (node (ref "V8") (pin "4") (pinfunction "4_4") (pintype "passive"))
      (node (ref "V8") (pin "5") (pinfunction "5_5") (pintype "passive"))
      (node (ref "VCC") (pin "1") (pinfunction "1_1") (pintype "passive"))
      (node (ref "VCC") (pin "2") (pinfunction "2_2") (pintype "passive"))
      (node (ref "VCC") (pin "3") (pinfunction "3_3") (pintype "passive"))
      (node (ref "VCC") (pin "4") (pinfunction "4_4") (pintype "passive"))
      (node (ref "VCC") (pin "5") (pinfunction "5_5") (pintype "passive"))
      (node (ref "VCC") (pin "6") (pinfunction "6_6") (pintype "passive"))
    )
    (net (code "26") (name "GND") (class "Default")
      (node (ref "ATMEGA328P") (pin "21") (pinfunction "AGND_21") (pintype "bidirectional"))
      (node (ref "ATMEGA328P") (pin "3") (pinfunction "GND_3") (pintype "bidirectional"))
      (node (ref "ATMEGA328P") (pin "5") (pinfunction "GND_5") (pintype "bidirectional"))
      (node (ref "C1") (pin "2") (pinfunction "2_2") (pintype "passive"))
      (node (ref "C2") (pin "-") (pinfunction "-_-") (pintype "passive"))
      (node (ref "C3") (pin "-") (pinfunction "-_-") (pintype "passive"))
      (node (ref "C6") (pin "2") (pinfunction "2_2") (pintype "passive"))
      (node (ref "C7") (pin "2") (pinfunction "2_2") (pintype "passive"))
      (node (ref "D1") (pin "C") (pinfunction "C_C") (pintype "passive"))
      (node (ref "D2") (pin "C") (pinfunction "C_C") (pintype "passive"))
      (node (ref "DIGITAL2") (pin "4") (pinfunction "4_4") (pintype "passive"))
      (node (ref "G0") (pin "1") (pinfunction "1_1") (pintype "passive"))
      (node (ref "G0") (pin "2") (pinfunction "2_2") (pintype "passive"))
      (node (ref "G0") (pin "3") (pinfunction "3_3") (pintype "passive"))
      (node (ref "G0") (pin "4") (pinfunction "4_4") (pintype "passive"))
      (node (ref "G0") (pin "5") (pinfunction "5_5") (pintype "passive"))
      (node (ref "G1") (pin "1") (pinfunction "1_1") (pintype "passive"))
      (node (ref "G1") (pin "2") (pinfunction "2_2") (pintype "passive"))
      (node (ref "G1") (pin "3") (pinfunction "3_3") (pintype "passive"))
      (node (ref "G1") (pin "4") (pinfunction "4_4") (pintype "passive"))
      (node (ref "G1") (pin "5") (pinfunction "5_5") (pintype "passive"))
      (node (ref "G2") (pin "1") (pinfunction "1_1") (pintype "passive"))
      (node (ref "G2") (pin "2") (pinfunction "2_2") (pintype "passive"))
      (node (ref "G2") (pin "3") (pinfunction "3_3") (pintype "passive"))
      (node (ref "G2") (pin "4") (pinfunction "4_4") (pintype "passive"))
      (node (ref "G2") (pin "5") (pinfunction "5_5") (pintype "passive"))
      (node (ref "G5") (pin "1") (pinfunction "1_1") (pintype "passive"))
      (node (ref "G5") (pin "2") (pinfunction "2_2") (pintype "passive"))
      (node (ref "G5") (pin "3") (pinfunction "3_3") (pintype "passive"))
      (node (ref "G5") (pin "4") (pinfunction "4_4") (pintype "passive"))
      (node (ref "G5") (pin "5") (pinfunction "5_5") (pintype "passive"))
      (node (ref "G6") (pin "1") (pinfunction "1_1") (pintype "passive"))
      (node (ref "G6") (pin "2") (pinfunction "2_2") (pintype "passive"))
      (node (ref "G6") (pin "3") (pinfunction "3_3") (pintype "passive"))
      (node (ref "G6") (pin "4") (pinfunction "4_4") (pintype "passive"))
      (node (ref "G6") (pin "5") (pinfunction "5_5") (pintype "passive"))
      (node (ref "G7") (pin "1") (pinfunction "1_1") (pintype "passive"))
      (node (ref "G7") (pin "2") (pinfunction "2_2") (pintype "passive"))
      (node (ref "G7") (pin "3") (pinfunction "3_3") (pintype "passive"))
      (node (ref "G7") (pin "4") (pinfunction "4_4") (pintype "passive"))
      (node (ref "G7") (pin "5") (pinfunction "5_5") (pintype "passive"))
      (node (ref "G8") (pin "1") (pinfunction "1_1") (pintype "passive"))
      (node (ref "G8") (pin "2") (pinfunction "2_2") (pintype "passive"))
      (node (ref "G8") (pin "3") (pinfunction "3_3") (pintype "passive"))
      (node (ref "G8") (pin "4") (pinfunction "4_4") (pintype "passive"))
      (node (ref "G8") (pin "5") (pinfunction "5_5") (pintype "passive"))
      (node (ref "G9") (pin "1") (pinfunction "1_1") (pintype "passive"))
      (node (ref "G9") (pin "2") (pinfunction "2_2") (pintype "passive"))
      (node (ref "G9") (pin "3") (pinfunction "3_3") (pintype "passive"))
      (node (ref "G9") (pin "4") (pinfunction "4_4") (pintype "passive"))
      (node (ref "G9") (pin "5") (pinfunction "5_5") (pintype "passive"))
      (node (ref "GND") (pin "1") (pinfunction "1_1") (pintype "passive"))
      (node (ref "GND") (pin "2") (pinfunction "2_2") (pintype "passive"))
      (node (ref "GND") (pin "3") (pinfunction "3_3") (pintype "passive"))
      (node (ref "GND") (pin "4") (pinfunction "4_4") (pintype "passive"))
      (node (ref "GND") (pin "5") (pinfunction "5_5") (pintype "passive"))
      (node (ref "GND") (pin "6") (pinfunction "6_6") (pintype "passive"))
      (node (ref "I2C") (pin "4") (pinfunction "4_4") (pintype "passive"))
      (node (ref "J1") (pin "GND") (pinfunction "GND_GND") (pintype "bidirectional"))
      (node (ref "J1") (pin "GNDBREAK") (pinfunction "GNDBREAK_GNDBREAK") (pintype "bidirectional"))
      (node (ref "POWER") (pin "2") (pinfunction "2_2") (pintype "passive"))
      (node (ref "POWER") (pin "3") (pinfunction "3_3") (pintype "passive"))
      (node (ref "R3") (pin "1") (pinfunction "1_1") (pintype "passive"))
      (node (ref "S1") (pin "1") (pinfunction "1_1") (pintype "passive"))
      (node (ref "S1") (pin "2") (pinfunction "2_2") (pintype "passive"))
      (node (ref "SPI") (pin "6") (pinfunction "6_6") (pintype "passive"))
      (node (ref "UART") (pin "5") (pinfunction "5_5") (pintype "passive"))
      (node (ref "UART2") (pin "5") (pinfunction "5_5") (pintype "passive"))
      (node (ref "Y2") (pin "2") (pinfunction "2_2") (pintype "passive"))
    )
    (net (code "27") (name "Net-(ATMEGA328P-PB6(XTAL1{slash}TOSC1))") (class "Default")
      (node (ref "ATMEGA328P") (pin "7") (pinfunction "PB6(XTAL1/TOSC1)_7") (pintype "bidirectional"))
      (node (ref "Y2") (pin "1") (pinfunction "1_1") (pintype "passive"))
    )
    (net (code "28") (name "Net-(ATMEGA328P-PB7(XTAL2{slash}TOSC2))") (class "Default")
      (node (ref "ATMEGA328P") (pin "8") (pinfunction "PB7(XTAL2/TOSC2)_8") (pintype "bidirectional"))
      (node (ref "Y2") (pin "3") (pinfunction "3_3") (pintype "passive"))
    )
    (net (code "29") (name "Net-(D1-PadA)") (class "Default")
      (node (ref "D1") (pin "A") (pinfunction "A_A") (pintype "passive"))
      (node (ref "R1") (pin "1") (pinfunction "1_1") (pintype "passive"))
    )
    (net (code "30") (name "Net-(D2-PadA)") (class "Default")
      (node (ref "D2") (pin "A") (pinfunction "A_A") (pintype "passive"))
      (node (ref "R6") (pin "1") (pinfunction "1_1") (pintype "passive"))
    )
    (net (code "31") (name "Net-(J2-Pad1)") (class "Default")
      (node (ref "J2") (pin "1") (pinfunction "1_1") (pintype "passive"))
      (node (ref "J2") (pin "2") (pinfunction "2_2") (pintype "passive"))
      (node (ref "J2") (pin "3") (pinfunction "3_3") (pintype "passive"))
      (node (ref "J2") (pin "4") (pinfunction "4_4") (pintype "passive"))
      (node (ref "J2") (pin "5") (pinfunction "5_5") (pintype "passive"))
      (node (ref "J27") (pin "1") (pinfunction "1_1") (pintype "passive"))
      (node (ref "J27") (pin "2") (pinfunction "2_2") (pintype "passive"))
      (node (ref "J27") (pin "3") (pinfunction "3_3") (pintype "passive"))
      (node (ref "J27") (pin "4") (pinfunction "4_4") (pintype "passive"))
      (node (ref "J27") (pin "5") (pinfunction "5_5") (pintype "passive"))
    )
    (net (code "32") (name "Net-(J3-Pad1)") (class "Default")
      (node (ref "J3") (pin "1") (pinfunction "1_1") (pintype "passive"))
      (node (ref "J3") (pin "2") (pinfunction "2_2") (pintype "passive"))
      (node (ref "J3") (pin "3") (pinfunction "3_3") (pintype "passive"))
      (node (ref "J3") (pin "4") (pinfunction "4_4") (pintype "passive"))
      (node (ref "J3") (pin "5") (pinfunction "5_5") (pintype "passive"))
      (node (ref "J4") (pin "1") (pinfunction "1_1") (pintype "passive"))
      (node (ref "J4") (pin "2") (pinfunction "2_2") (pintype "passive"))
      (node (ref "J4") (pin "3") (pinfunction "3_3") (pintype "passive"))
      (node (ref "J4") (pin "4") (pinfunction "4_4") (pintype "passive"))
      (node (ref "J4") (pin "5") (pinfunction "5_5") (pintype "passive"))
    )
    (net (code "33") (name "Net-(J5-Pad1)") (class "Default")
      (node (ref "J5") (pin "1") (pinfunction "1_1") (pintype "passive"))
      (node (ref "J5") (pin "2") (pinfunction "2_2") (pintype "passive"))
      (node (ref "J5") (pin "3") (pinfunction "3_3") (pintype "passive"))
      (node (ref "J5") (pin "4") (pinfunction "4_4") (pintype "passive"))
      (node (ref "J5") (pin "5") (pinfunction "5_5") (pintype "passive"))
      (node (ref "J65") (pin "1") (pinfunction "1_1") (pintype "passive"))
      (node (ref "J65") (pin "2") (pinfunction "2_2") (pintype "passive"))
      (node (ref "J65") (pin "3") (pinfunction "3_3") (pintype "passive"))
      (node (ref "J65") (pin "4") (pinfunction "4_4") (pintype "passive"))
      (node (ref "J65") (pin "5") (pinfunction "5_5") (pintype "passive"))
    )
    (net (code "34") (name "Net-(J6-Pad1)") (class "Default")
      (node (ref "J6") (pin "1") (pinfunction "1_1") (pintype "passive"))
      (node (ref "J6") (pin "2") (pinfunction "2_2") (pintype "passive"))
      (node (ref "J6") (pin "3") (pinfunction "3_3") (pintype "passive"))
      (node (ref "J6") (pin "4") (pinfunction "4_4") (pintype "passive"))
      (node (ref "J6") (pin "5") (pinfunction "5_5") (pintype "passive"))
      (node (ref "J7") (pin "1") (pinfunction "1_1") (pintype "passive"))
      (node (ref "J7") (pin "2") (pinfunction "2_2") (pintype "passive"))
      (node (ref "J7") (pin "3") (pinfunction "3_3") (pintype "passive"))
      (node (ref "J7") (pin "4") (pinfunction "4_4") (pintype "passive"))
      (node (ref "J7") (pin "5") (pinfunction "5_5") (pintype "passive"))
    )
    (net (code "35") (name "Net-(J8-Pad1)") (class "Default")
      (node (ref "J8") (pin "1") (pinfunction "1_1") (pintype "passive"))
      (node (ref "J8") (pin "2") (pinfunction "2_2") (pintype "passive"))
      (node (ref "J8") (pin "3") (pinfunction "3_3") (pintype "passive"))
      (node (ref "J8") (pin "4") (pinfunction "4_4") (pintype "passive"))
      (node (ref "J8") (pin "5") (pinfunction "5_5") (pintype "passive"))
      (node (ref "J9") (pin "1") (pinfunction "1_1") (pintype "passive"))
      (node (ref "J9") (pin "2") (pinfunction "2_2") (pintype "passive"))
      (node (ref "J9") (pin "3") (pinfunction "3_3") (pintype "passive"))
      (node (ref "J9") (pin "4") (pinfunction "4_4") (pintype "passive"))
      (node (ref "J9") (pin "5") (pinfunction "5_5") (pintype "passive"))
    )
    (net (code "36") (name "Net-(J10-Pad1)") (class "Default")
      (node (ref "J10") (pin "1") (pinfunction "1_1") (pintype "passive"))
      (node (ref "J10") (pin "2") (pinfunction "2_2") (pintype "passive"))
      (node (ref "J10") (pin "3") (pinfunction "3_3") (pintype "passive"))
      (node (ref "J10") (pin "4") (pinfunction "4_4") (pintype "passive"))
      (node (ref "J10") (pin "5") (pinfunction "5_5") (pintype "passive"))
      (node (ref "J11") (pin "1") (pinfunction "1_1") (pintype "passive"))
      (node (ref "J11") (pin "2") (pinfunction "2_2") (pintype "passive"))
      (node (ref "J11") (pin "3") (pinfunction "3_3") (pintype "passive"))
      (node (ref "J11") (pin "4") (pinfunction "4_4") (pintype "passive"))
      (node (ref "J11") (pin "5") (pinfunction "5_5") (pintype "passive"))
    )
    (net (code "37") (name "Net-(J12-Pad1)") (class "Default")
      (node (ref "J12") (pin "1") (pinfunction "1_1") (pintype "passive"))
      (node (ref "J12") (pin "2") (pinfunction "2_2") (pintype "passive"))
      (node (ref "J12") (pin "3") (pinfunction "3_3") (pintype "passive"))
      (node (ref "J12") (pin "4") (pinfunction "4_4") (pintype "passive"))
      (node (ref "J12") (pin "5") (pinfunction "5_5") (pintype "passive"))
      (node (ref "J66") (pin "1") (pinfunction "1_1") (pintype "passive"))
      (node (ref "J66") (pin "2") (pinfunction "2_2") (pintype "passive"))
      (node (ref "J66") (pin "3") (pinfunction "3_3") (pintype "passive"))
      (node (ref "J66") (pin "4") (pinfunction "4_4") (pintype "passive"))
      (node (ref "J66") (pin "5") (pinfunction "5_5") (pintype "passive"))
    )
    (net (code "38") (name "Net-(J13-Pad1)") (class "Default")
      (node (ref "J13") (pin "1") (pinfunction "1_1") (pintype "passive"))
      (node (ref "J13") (pin "2") (pinfunction "2_2") (pintype "passive"))
      (node (ref "J13") (pin "3") (pinfunction "3_3") (pintype "passive"))
      (node (ref "J13") (pin "4") (pinfunction "4_4") (pintype "passive"))
      (node (ref "J13") (pin "5") (pinfunction "5_5") (pintype "passive"))
      (node (ref "J22") (pin "1") (pinfunction "1_1") (pintype "passive"))
      (node (ref "J22") (pin "2") (pinfunction "2_2") (pintype "passive"))
      (node (ref "J22") (pin "3") (pinfunction "3_3") (pintype "passive"))
      (node (ref "J22") (pin "4") (pinfunction "4_4") (pintype "passive"))
      (node (ref "J22") (pin "5") (pinfunction "5_5") (pintype "passive"))
    )
    (net (code "39") (name "Net-(J14-Pad1)") (class "Default")
      (node (ref "J14") (pin "1") (pinfunction "1_1") (pintype "passive"))
      (node (ref "J14") (pin "2") (pinfunction "2_2") (pintype "passive"))
      (node (ref "J14") (pin "3") (pinfunction "3_3") (pintype "passive"))
      (node (ref "J14") (pin "4") (pinfunction "4_4") (pintype "passive"))
      (node (ref "J14") (pin "5") (pinfunction "5_5") (pintype "passive"))
      (node (ref "J31") (pin "1") (pinfunction "1_1") (pintype "passive"))
      (node (ref "J31") (pin "2") (pinfunction "2_2") (pintype "passive"))
      (node (ref "J31") (pin "3") (pinfunction "3_3") (pintype "passive"))
      (node (ref "J31") (pin "4") (pinfunction "4_4") (pintype "passive"))
      (node (ref "J31") (pin "5") (pinfunction "5_5") (pintype "passive"))
    )
    (net (code "40") (name "Net-(J15-Pad1)") (class "Default")
      (node (ref "J15") (pin "1") (pinfunction "1_1") (pintype "passive"))
      (node (ref "J15") (pin "2") (pinfunction "2_2") (pintype "passive"))
      (node (ref "J15") (pin "3") (pinfunction "3_3") (pintype "passive"))
      (node (ref "J15") (pin "4") (pinfunction "4_4") (pintype "passive"))
      (node (ref "J15") (pin "5") (pinfunction "5_5") (pintype "passive"))
      (node (ref "J21") (pin "1") (pinfunction "1_1") (pintype "passive"))
      (node (ref "J21") (pin "2") (pinfunction "2_2") (pintype "passive"))
      (node (ref "J21") (pin "3") (pinfunction "3_3") (pintype "passive"))
      (node (ref "J21") (pin "4") (pinfunction "4_4") (pintype "passive"))
      (node (ref "J21") (pin "5") (pinfunction "5_5") (pintype "passive"))
    )
    (net (code "41") (name "Net-(J16-Pad1)") (class "Default")
      (node (ref "J16") (pin "1") (pinfunction "1_1") (pintype "passive"))
      (node (ref "J16") (pin "2") (pinfunction "2_2") (pintype "passive"))
      (node (ref "J16") (pin "3") (pinfunction "3_3") (pintype "passive"))
      (node (ref "J16") (pin "4") (pinfunction "4_4") (pintype "passive"))
      (node (ref "J16") (pin "5") (pinfunction "5_5") (pintype "passive"))
      (node (ref "J29") (pin "1") (pinfunction "1_1") (pintype "passive"))
      (node (ref "J29") (pin "2") (pinfunction "2_2") (pintype "passive"))
      (node (ref "J29") (pin "3") (pinfunction "3_3") (pintype "passive"))
      (node (ref "J29") (pin "4") (pinfunction "4_4") (pintype "passive"))
      (node (ref "J29") (pin "5") (pinfunction "5_5") (pintype "passive"))
    )
    (net (code "42") (name "Net-(J17-Pad1)") (class "Default")
      (node (ref "J17") (pin "1") (pinfunction "1_1") (pintype "passive"))
      (node (ref "J17") (pin "2") (pinfunction "2_2") (pintype "passive"))
      (node (ref "J17") (pin "3") (pinfunction "3_3") (pintype "passive"))
      (node (ref "J17") (pin "4") (pinfunction "4_4") (pintype "passive"))
      (node (ref "J17") (pin "5") (pinfunction "5_5") (pintype "passive"))
      (node (ref "J30") (pin "1") (pinfunction "1_1") (pintype "passive"))
      (node (ref "J30") (pin "2") (pinfunction "2_2") (pintype "passive"))
      (node (ref "J30") (pin "3") (pinfunction "3_3") (pintype "passive"))
      (node (ref "J30") (pin "4") (pinfunction "4_4") (pintype "passive"))
      (node (ref "J30") (pin "5") (pinfunction "5_5") (pintype "passive"))
    )
    (net (code "43") (name "Net-(J18-Pad1)") (class "Default")
      (node (ref "J18") (pin "1") (pinfunction "1_1") (pintype "passive"))
      (node (ref "J18") (pin "2") (pinfunction "2_2") (pintype "passive"))
      (node (ref "J18") (pin "3") (pinfunction "3_3") (pintype "passive"))
      (node (ref "J18") (pin "4") (pinfunction "4_4") (pintype "passive"))
      (node (ref "J18") (pin "5") (pinfunction "5_5") (pintype "passive"))
      (node (ref "J26") (pin "1") (pinfunction "1_1") (pintype "passive"))
      (node (ref "J26") (pin "2") (pinfunction "2_2") (pintype "passive"))
      (node (ref "J26") (pin "3") (pinfunction "3_3") (pintype "passive"))
      (node (ref "J26") (pin "4") (pinfunction "4_4") (pintype "passive"))
      (node (ref "J26") (pin "5") (pinfunction "5_5") (pintype "passive"))
    )
    (net (code "44") (name "Net-(J19-Pad1)") (class "Default")
      (node (ref "J19") (pin "1") (pinfunction "1_1") (pintype "passive"))
      (node (ref "J19") (pin "2") (pinfunction "2_2") (pintype "passive"))
      (node (ref "J19") (pin "3") (pinfunction "3_3") (pintype "passive"))
      (node (ref "J19") (pin "4") (pinfunction "4_4") (pintype "passive"))
      (node (ref "J19") (pin "5") (pinfunction "5_5") (pintype "passive"))
      (node (ref "J54") (pin "1") (pinfunction "1_1") (pintype "passive"))
      (node (ref "J54") (pin "2") (pinfunction "2_2") (pintype "passive"))
      (node (ref "J54") (pin "3") (pinfunction "3_3") (pintype "passive"))
      (node (ref "J54") (pin "4") (pinfunction "4_4") (pintype "passive"))
      (node (ref "J54") (pin "5") (pinfunction "5_5") (pintype "passive"))
    )
    (net (code "45") (name "Net-(J20-Pad1)") (class "Default")
      (node (ref "J20") (pin "1") (pinfunction "1_1") (pintype "passive"))
      (node (ref "J20") (pin "2") (pinfunction "2_2") (pintype "passive"))
      (node (ref "J20") (pin "3") (pinfunction "3_3") (pintype "passive"))
      (node (ref "J20") (pin "4") (pinfunction "4_4") (pintype "passive"))
      (node (ref "J20") (pin "5") (pinfunction "5_5") (pintype "passive"))
      (node (ref "J61") (pin "1") (pinfunction "1_1") (pintype "passive"))
      (node (ref "J61") (pin "2") (pinfunction "2_2") (pintype "passive"))
      (node (ref "J61") (pin "3") (pinfunction "3_3") (pintype "passive"))
      (node (ref "J61") (pin "4") (pinfunction "4_4") (pintype "passive"))
      (node (ref "J61") (pin "5") (pinfunction "5_5") (pintype "passive"))
    )
    (net (code "46") (name "Net-(J23-Pad1)") (class "Default")
      (node (ref "J23") (pin "1") (pinfunction "1_1") (pintype "passive"))
      (node (ref "J23") (pin "2") (pinfunction "2_2") (pintype "passive"))
      (node (ref "J23") (pin "3") (pinfunction "3_3") (pintype "passive"))
      (node (ref "J23") (pin "4") (pinfunction "4_4") (pintype "passive"))
      (node (ref "J23") (pin "5") (pinfunction "5_5") (pintype "passive"))
      (node (ref "J32") (pin "1") (pinfunction "1_1") (pintype "passive"))
      (node (ref "J32") (pin "2") (pinfunction "2_2") (pintype "passive"))
      (node (ref "J32") (pin "3") (pinfunction "3_3") (pintype "passive"))
      (node (ref "J32") (pin "4") (pinfunction "4_4") (pintype "passive"))
      (node (ref "J32") (pin "5") (pinfunction "5_5") (pintype "passive"))
    )
    (net (code "47") (name "Net-(J24-Pad1)") (class "Default")
      (node (ref "J24") (pin "1") (pinfunction "1_1") (pintype "passive"))
      (node (ref "J24") (pin "2") (pinfunction "2_2") (pintype "passive"))
      (node (ref "J24") (pin "3") (pinfunction "3_3") (pintype "passive"))
      (node (ref "J24") (pin "4") (pinfunction "4_4") (pintype "passive"))
      (node (ref "J24") (pin "5") (pinfunction "5_5") (pintype "passive"))
      (node (ref "J33") (pin "1") (pinfunction "1_1") (pintype "passive"))
      (node (ref "J33") (pin "2") (pinfunction "2_2") (pintype "passive"))
      (node (ref "J33") (pin "3") (pinfunction "3_3") (pintype "passive"))
      (node (ref "J33") (pin "4") (pinfunction "4_4") (pintype "passive"))
      (node (ref "J33") (pin "5") (pinfunction "5_5") (pintype "passive"))
    )
    (net (code "48") (name "Net-(J25-Pad1)") (class "Default")
      (node (ref "J25") (pin "1") (pinfunction "1_1") (pintype "passive"))
      (node (ref "J25") (pin "2") (pinfunction "2_2") (pintype "passive"))
      (node (ref "J25") (pin "3") (pinfunction "3_3") (pintype "passive"))
      (node (ref "J25") (pin "4") (pinfunction "4_4") (pintype "passive"))
      (node (ref "J25") (pin "5") (pinfunction "5_5") (pintype "passive"))
      (node (ref "J41") (pin "1") (pinfunction "1_1") (pintype "passive"))
      (node (ref "J41") (pin "2") (pinfunction "2_2") (pintype "passive"))
      (node (ref "J41") (pin "3") (pinfunction "3_3") (pintype "passive"))
      (node (ref "J41") (pin "4") (pinfunction "4_4") (pintype "passive"))
      (node (ref "J41") (pin "5") (pinfunction "5_5") (pintype "passive"))
    )
    (net (code "49") (name "Net-(J28-Pad1)") (class "Default")
      (node (ref "J28") (pin "1") (pinfunction "1_1") (pintype "passive"))
      (node (ref "J28") (pin "2") (pinfunction "2_2") (pintype "passive"))
      (node (ref "J28") (pin "3") (pinfunction "3_3") (pintype "passive"))
      (node (ref "J28") (pin "4") (pinfunction "4_4") (pintype "passive"))
      (node (ref "J28") (pin "5") (pinfunction "5_5") (pintype "passive"))
      (node (ref "J67") (pin "1") (pinfunction "1_1") (pintype "passive"))
      (node (ref "J67") (pin "2") (pinfunction "2_2") (pintype "passive"))
      (node (ref "J67") (pin "3") (pinfunction "3_3") (pintype "passive"))
      (node (ref "J67") (pin "4") (pinfunction "4_4") (pintype "passive"))
      (node (ref "J67") (pin "5") (pinfunction "5_5") (pintype "passive"))
    )
    (net (code "50") (name "Net-(J34-Pad1)") (class "Default")
      (node (ref "J34") (pin "1") (pinfunction "1_1") (pintype "passive"))
      (node (ref "J34") (pin "2") (pinfunction "2_2") (pintype "passive"))
      (node (ref "J34") (pin "3") (pinfunction "3_3") (pintype "passive"))
      (node (ref "J34") (pin "4") (pinfunction "4_4") (pintype "passive"))
      (node (ref "J34") (pin "5") (pinfunction "5_5") (pintype "passive"))
      (node (ref "J35") (pin "1") (pinfunction "1_1") (pintype "passive"))
      (node (ref "J35") (pin "2") (pinfunction "2_2") (pintype "passive"))
      (node (ref "J35") (pin "3") (pinfunction "3_3") (pintype "passive"))
      (node (ref "J35") (pin "4") (pinfunction "4_4") (pintype "passive"))
      (node (ref "J35") (pin "5") (pinfunction "5_5") (pintype "passive"))
    )
    (net (code "51") (name "Net-(J36-Pad1)") (class "Default")
      (node (ref "J36") (pin "1") (pinfunction "1_1") (pintype "passive"))
      (node (ref "J36") (pin "2") (pinfunction "2_2") (pintype "passive"))
      (node (ref "J36") (pin "3") (pinfunction "3_3") (pintype "passive"))
      (node (ref "J36") (pin "4") (pinfunction "4_4") (pintype "passive"))
      (node (ref "J36") (pin "5") (pinfunction "5_5") (pintype "passive"))
      (node (ref "J42") (pin "1") (pinfunction "1_1") (pintype "passive"))
      (node (ref "J42") (pin "2") (pinfunction "2_2") (pintype "passive"))
      (node (ref "J42") (pin "3") (pinfunction "3_3") (pintype "passive"))
      (node (ref "J42") (pin "4") (pinfunction "4_4") (pintype "passive"))
      (node (ref "J42") (pin "5") (pinfunction "5_5") (pintype "passive"))
    )
    (net (code "52") (name "Net-(J37-Pad1)") (class "Default")
      (node (ref "J37") (pin "1") (pinfunction "1_1") (pintype "passive"))
      (node (ref "J37") (pin "2") (pinfunction "2_2") (pintype "passive"))
      (node (ref "J37") (pin "3") (pinfunction "3_3") (pintype "passive"))
      (node (ref "J37") (pin "4") (pinfunction "4_4") (pintype "passive"))
      (node (ref "J37") (pin "5") (pinfunction "5_5") (pintype "passive"))
      (node (ref "J71") (pin "1") (pinfunction "1_1") (pintype "passive"))
      (node (ref "J71") (pin "2") (pinfunction "2_2") (pintype "passive"))
      (node (ref "J71") (pin "3") (pinfunction "3_3") (pintype "passive"))
      (node (ref "J71") (pin "4") (pinfunction "4_4") (pintype "passive"))
      (node (ref "J71") (pin "5") (pinfunction "5_5") (pintype "passive"))
    )
    (net (code "53") (name "Net-(J38-Pad1)") (class "Default")
      (node (ref "J38") (pin "1") (pinfunction "1_1") (pintype "passive"))
      (node (ref "J38") (pin "2") (pinfunction "2_2") (pintype "passive"))
      (node (ref "J38") (pin "3") (pinfunction "3_3") (pintype "passive"))
      (node (ref "J38") (pin "4") (pinfunction "4_4") (pintype "passive"))
      (node (ref "J38") (pin "5") (pinfunction "5_5") (pintype "passive"))
      (node (ref "J72") (pin "1") (pinfunction "1_1") (pintype "passive"))
      (node (ref "J72") (pin "2") (pinfunction "2_2") (pintype "passive"))
      (node (ref "J72") (pin "3") (pinfunction "3_3") (pintype "passive"))
      (node (ref "J72") (pin "4") (pinfunction "4_4") (pintype "passive"))
      (node (ref "J72") (pin "5") (pinfunction "5_5") (pintype "passive"))
    )
    (net (code "54") (name "Net-(J39-Pad1)") (class "Default")
      (node (ref "J39") (pin "1") (pinfunction "1_1") (pintype "passive"))
      (node (ref "J39") (pin "2") (pinfunction "2_2") (pintype "passive"))
      (node (ref "J39") (pin "3") (pinfunction "3_3") (pintype "passive"))
      (node (ref "J39") (pin "4") (pinfunction "4_4") (pintype "passive"))
      (node (ref "J39") (pin "5") (pinfunction "5_5") (pintype "passive"))
      (node (ref "J40") (pin "1") (pinfunction "1_1") (pintype "passive"))
      (node (ref "J40") (pin "2") (pinfunction "2_2") (pintype "passive"))
      (node (ref "J40") (pin "3") (pinfunction "3_3") (pintype "passive"))
      (node (ref "J40") (pin "4") (pinfunction "4_4") (pintype "passive"))
      (node (ref "J40") (pin "5") (pinfunction "5_5") (pintype "passive"))
    )
    (net (code "55") (name "Net-(J43-Pad1)") (class "Default")
      (node (ref "J43") (pin "1") (pinfunction "1_1") (pintype "passive"))
      (node (ref "J43") (pin "2") (pinfunction "2_2") (pintype "passive"))
      (node (ref "J43") (pin "3") (pinfunction "3_3") (pintype "passive"))
      (node (ref "J43") (pin "4") (pinfunction "4_4") (pintype "passive"))
      (node (ref "J43") (pin "5") (pinfunction "5_5") (pintype "passive"))
      (node (ref "J44") (pin "1") (pinfunction "1_1") (pintype "passive"))
      (node (ref "J44") (pin "2") (pinfunction "2_2") (pintype "passive"))
      (node (ref "J44") (pin "3") (pinfunction "3_3") (pintype "passive"))
      (node (ref "J44") (pin "4") (pinfunction "4_4") (pintype "passive"))
      (node (ref "J44") (pin "5") (pinfunction "5_5") (pintype "passive"))
    )
    (net (code "56") (name "Net-(J45-Pad1)") (class "Default")
      (node (ref "J45") (pin "1") (pinfunction "1_1") (pintype "passive"))
      (node (ref "J45") (pin "2") (pinfunction "2_2") (pintype "passive"))
      (node (ref "J45") (pin "3") (pinfunction "3_3") (pintype "passive"))
      (node (ref "J45") (pin "4") (pinfunction "4_4") (pintype "passive"))
      (node (ref "J45") (pin "5") (pinfunction "5_5") (pintype "passive"))
      (node (ref "J46") (pin "1") (pinfunction "1_1") (pintype "passive"))
      (node (ref "J46") (pin "2") (pinfunction "2_2") (pintype "passive"))
      (node (ref "J46") (pin "3") (pinfunction "3_3") (pintype "passive"))
      (node (ref "J46") (pin "4") (pinfunction "4_4") (pintype "passive"))
      (node (ref "J46") (pin "5") (pinfunction "5_5") (pintype "passive"))
    )
    (net (code "57") (name "Net-(J47-Pad1)") (class "Default")
      (node (ref "J47") (pin "1") (pinfunction "1_1") (pintype "passive"))
      (node (ref "J47") (pin "2") (pinfunction "2_2") (pintype "passive"))
      (node (ref "J47") (pin "3") (pinfunction "3_3") (pintype "passive"))
      (node (ref "J47") (pin "4") (pinfunction "4_4") (pintype "passive"))
      (node (ref "J47") (pin "5") (pinfunction "5_5") (pintype "passive"))
      (node (ref "J48") (pin "1") (pinfunction "1_1") (pintype "passive"))
      (node (ref "J48") (pin "2") (pinfunction "2_2") (pintype "passive"))
      (node (ref "J48") (pin "3") (pinfunction "3_3") (pintype "passive"))
      (node (ref "J48") (pin "4") (pinfunction "4_4") (pintype "passive"))
      (node (ref "J48") (pin "5") (pinfunction "5_5") (pintype "passive"))
    )
    (net (code "58") (name "Net-(J49-Pad1)") (class "Default")
      (node (ref "J49") (pin "1") (pinfunction "1_1") (pintype "passive"))
      (node (ref "J49") (pin "2") (pinfunction "2_2") (pintype "passive"))
      (node (ref "J49") (pin "3") (pinfunction "3_3") (pintype "passive"))
      (node (ref "J49") (pin "4") (pinfunction "4_4") (pintype "passive"))
      (node (ref "J49") (pin "5") (pinfunction "5_5") (pintype "passive"))
      (node (ref "J53") (pin "1") (pinfunction "1_1") (pintype "passive"))
      (node (ref "J53") (pin "2") (pinfunction "2_2") (pintype "passive"))
      (node (ref "J53") (pin "3") (pinfunction "3_3") (pintype "passive"))
      (node (ref "J53") (pin "4") (pinfunction "4_4") (pintype "passive"))
      (node (ref "J53") (pin "5") (pinfunction "5_5") (pintype "passive"))
    )
    (net (code "59") (name "Net-(J50-Pad1)") (class "Default")
      (node (ref "J50") (pin "1") (pinfunction "1_1") (pintype "passive"))
      (node (ref "J50") (pin "2") (pinfunction "2_2") (pintype "passive"))
      (node (ref "J50") (pin "3") (pinfunction "3_3") (pintype "passive"))
      (node (ref "J50") (pin "4") (pinfunction "4_4") (pintype "passive"))
      (node (ref "J50") (pin "5") (pinfunction "5_5") (pintype "passive"))
      (node (ref "J51") (pin "1") (pinfunction "1_1") (pintype "passive"))
      (node (ref "J51") (pin "2") (pinfunction "2_2") (pintype "passive"))
      (node (ref "J51") (pin "3") (pinfunction "3_3") (pintype "passive"))
      (node (ref "J51") (pin "4") (pinfunction "4_4") (pintype "passive"))
      (node (ref "J51") (pin "5") (pinfunction "5_5") (pintype "passive"))
    )
    (net (code "60") (name "Net-(J52-Pad1)") (class "Default")
      (node (ref "J52") (pin "1") (pinfunction "1_1") (pintype "passive"))
      (node (ref "J52") (pin "2") (pinfunction "2_2") (pintype "passive"))
      (node (ref "J52") (pin "3") (pinfunction "3_3") (pintype "passive"))
      (node (ref "J52") (pin "4") (pinfunction "4_4") (pintype "passive"))
      (node (ref "J52") (pin "5") (pinfunction "5_5") (pintype "passive"))
      (node (ref "J58") (pin "1") (pinfunction "1_1") (pintype "passive"))
      (node (ref "J58") (pin "2") (pinfunction "2_2") (pintype "passive"))
      (node (ref "J58") (pin "3") (pinfunction "3_3") (pintype "passive"))
      (node (ref "J58") (pin "4") (pinfunction "4_4") (pintype "passive"))
      (node (ref "J58") (pin "5") (pinfunction "5_5") (pintype "passive"))
    )
    (net (code "61") (name "Net-(J55-Pad1)") (class "Default")
      (node (ref "J55") (pin "1") (pinfunction "1_1") (pintype "passive"))
      (node (ref "J55") (pin "2") (pinfunction "2_2") (pintype "passive"))
      (node (ref "J55") (pin "3") (pinfunction "3_3") (pintype "passive"))
      (node (ref "J55") (pin "4") (pinfunction "4_4") (pintype "passive"))
      (node (ref "J55") (pin "5") (pinfunction "5_5") (pintype "passive"))
      (node (ref "J56") (pin "1") (pinfunction "1_1") (pintype "passive"))
      (node (ref "J56") (pin "2") (pinfunction "2_2") (pintype "passive"))
      (node (ref "J56") (pin "3") (pinfunction "3_3") (pintype "passive"))
      (node (ref "J56") (pin "4") (pinfunction "4_4") (pintype "passive"))
      (node (ref "J56") (pin "5") (pinfunction "5_5") (pintype "passive"))
    )
    (net (code "62") (name "Net-(J57-Pad1)") (class "Default")
      (node (ref "J57") (pin "1") (pinfunction "1_1") (pintype "passive"))
      (node (ref "J57") (pin "2") (pinfunction "2_2") (pintype "passive"))
      (node (ref "J57") (pin "3") (pinfunction "3_3") (pintype "passive"))
      (node (ref "J57") (pin "4") (pinfunction "4_4") (pintype "passive"))
      (node (ref "J57") (pin "5") (pinfunction "5_5") (pintype "passive"))
      (node (ref "J62") (pin "1") (pinfunction "1_1") (pintype "passive"))
      (node (ref "J62") (pin "2") (pinfunction "2_2") (pintype "passive"))
      (node (ref "J62") (pin "3") (pinfunction "3_3") (pintype "passive"))
      (node (ref "J62") (pin "4") (pinfunction "4_4") (pintype "passive"))
      (node (ref "J62") (pin "5") (pinfunction "5_5") (pintype "passive"))
    )
    (net (code "63") (name "Net-(J59-Pad1)") (class "Default")
      (node (ref "J59") (pin "1") (pinfunction "1_1") (pintype "passive"))
      (node (ref "J59") (pin "2") (pinfunction "2_2") (pintype "passive"))
      (node (ref "J59") (pin "3") (pinfunction "3_3") (pintype "passive"))
      (node (ref "J59") (pin "4") (pinfunction "4_4") (pintype "passive"))
      (node (ref "J59") (pin "5") (pinfunction "5_5") (pintype "passive"))
      (node (ref "J60") (pin "1") (pinfunction "1_1") (pintype "passive"))
      (node (ref "J60") (pin "2") (pinfunction "2_2") (pintype "passive"))
      (node (ref "J60") (pin "3") (pinfunction "3_3") (pintype "passive"))
      (node (ref "J60") (pin "4") (pinfunction "4_4") (pintype "passive"))
      (node (ref "J60") (pin "5") (pinfunction "5_5") (pintype "passive"))
    )
    (net (code "64") (name "Net-(J63-Pad1)") (class "Default")
      (node (ref "J63") (pin "1") (pinfunction "1_1") (pintype "passive"))
      (node (ref "J63") (pin "2") (pinfunction "2_2") (pintype "passive"))
      (node (ref "J63") (pin "3") (pinfunction "3_3") (pintype "passive"))
      (node (ref "J63") (pin "4") (pinfunction "4_4") (pintype "passive"))
      (node (ref "J63") (pin "5") (pinfunction "5_5") (pintype "passive"))
      (node (ref "J64") (pin "1") (pinfunction "1_1") (pintype "passive"))
      (node (ref "J64") (pin "2") (pinfunction "2_2") (pintype "passive"))
      (node (ref "J64") (pin "3") (pinfunction "3_3") (pintype "passive"))
      (node (ref "J64") (pin "4") (pinfunction "4_4") (pintype "passive"))
      (node (ref "J64") (pin "5") (pinfunction "5_5") (pintype "passive"))
    )
    (net (code "65") (name "Net-(J68-Pad1)") (class "Default")
      (node (ref "J68") (pin "1") (pinfunction "1_1") (pintype "passive"))
      (node (ref "J68") (pin "2") (pinfunction "2_2") (pintype "passive"))
      (node (ref "J68") (pin "3") (pinfunction "3_3") (pintype "passive"))
      (node (ref "J68") (pin "4") (pinfunction "4_4") (pintype "passive"))
      (node (ref "J68") (pin "5") (pinfunction "5_5") (pintype "passive"))
      (node (ref "J69") (pin "1") (pinfunction "1_1") (pintype "passive"))
      (node (ref "J69") (pin "2") (pinfunction "2_2") (pintype "passive"))
      (node (ref "J69") (pin "3") (pinfunction "3_3") (pintype "passive"))
      (node (ref "J69") (pin "4") (pinfunction "4_4") (pintype "passive"))
      (node (ref "J69") (pin "5") (pinfunction "5_5") (pintype "passive"))
    )
    (net (code "66") (name "Net-(J70-Pad1)") (class "Default")
      (node (ref "J70") (pin "1") (pinfunction "1_1") (pintype "passive"))
      (node (ref "J70") (pin "2") (pinfunction "2_2") (pintype "passive"))
      (node (ref "J70") (pin "3") (pinfunction "3_3") (pintype "passive"))
      (node (ref "J70") (pin "4") (pinfunction "4_4") (pintype "passive"))
      (node (ref "J70") (pin "5") (pinfunction "5_5") (pintype "passive"))
      (node (ref "J75") (pin "1") (pinfunction "1_1") (pintype "passive"))
      (node (ref "J75") (pin "2") (pinfunction "2_2") (pintype "passive"))
      (node (ref "J75") (pin "3") (pinfunction "3_3") (pintype "passive"))
      (node (ref "J75") (pin "4") (pinfunction "4_4") (pintype "passive"))
      (node (ref "J75") (pin "5") (pinfunction "5_5") (pintype "passive"))
    )
    (net (code "67") (name "Net-(J76-Pad1)") (class "Default")
      (node (ref "J76") (pin "1") (pinfunction "1_1") (pintype "passive"))
      (node (ref "J76") (pin "2") (pinfunction "2_2") (pintype "passive"))
      (node (ref "J76") (pin "3") (pinfunction "3_3") (pintype "passive"))
      (node (ref "J76") (pin "4") (pinfunction "4_4") (pintype "passive"))
      (node (ref "J76") (pin "5") (pinfunction "5_5") (pintype "passive"))
      (node (ref "J77") (pin "1") (pinfunction "1_1") (pintype "passive"))
      (node (ref "J77") (pin "2") (pinfunction "2_2") (pintype "passive"))
      (node (ref "J77") (pin "3") (pinfunction "3_3") (pintype "passive"))
      (node (ref "J77") (pin "4") (pinfunction "4_4") (pintype "passive"))
      (node (ref "J77") (pin "5") (pinfunction "5_5") (pintype "passive"))
    )
    (net (code "68") (name "Net-(J78-Pad1)") (class "Default")
      (node (ref "J78") (pin "1") (pinfunction "1_1") (pintype "passive"))
      (node (ref "J78") (pin "2") (pinfunction "2_2") (pintype "passive"))
      (node (ref "J78") (pin "3") (pinfunction "3_3") (pintype "passive"))
      (node (ref "J78") (pin "4") (pinfunction "4_4") (pintype "passive"))
      (node (ref "J78") (pin "5") (pinfunction "5_5") (pintype "passive"))
      (node (ref "J79") (pin "1") (pinfunction "1_1") (pintype "passive"))
      (node (ref "J79") (pin "2") (pinfunction "2_2") (pintype "passive"))
      (node (ref "J79") (pin "3") (pinfunction "3_3") (pintype "passive"))
      (node (ref "J79") (pin "4") (pinfunction "4_4") (pintype "passive"))
      (node (ref "J79") (pin "5") (pinfunction "5_5") (pintype "passive"))
    )
    (net (code "69") (name "Net-(J80-Pad1)") (class "Default")
      (node (ref "J80") (pin "1") (pinfunction "1_1") (pintype "passive"))
      (node (ref "J80") (pin "2") (pinfunction "2_2") (pintype "passive"))
      (node (ref "J80") (pin "3") (pinfunction "3_3") (pintype "passive"))
      (node (ref "J80") (pin "4") (pinfunction "4_4") (pintype "passive"))
      (node (ref "J80") (pin "5") (pinfunction "5_5") (pintype "passive"))
      (node (ref "J81") (pin "1") (pinfunction "1_1") (pintype "passive"))
      (node (ref "J81") (pin "2") (pinfunction "2_2") (pintype "passive"))
      (node (ref "J81") (pin "3") (pinfunction "3_3") (pintype "passive"))
      (node (ref "J81") (pin "4") (pinfunction "4_4") (pintype "passive"))
      (node (ref "J81") (pin "5") (pinfunction "5_5") (pintype "passive"))
    )
    (net (code "70") (name "Net-(J82-Pad1)") (class "Default")
      (node (ref "J82") (pin "1") (pinfunction "1_1") (pintype "passive"))
      (node (ref "J82") (pin "2") (pinfunction "2_2") (pintype "passive"))
      (node (ref "J82") (pin "3") (pinfunction "3_3") (pintype "passive"))
      (node (ref "J82") (pin "4") (pinfunction "4_4") (pintype "passive"))
      (node (ref "J82") (pin "5") (pinfunction "5_5") (pintype "passive"))
      (node (ref "J86") (pin "1") (pinfunction "1_1") (pintype "passive"))
      (node (ref "J86") (pin "2") (pinfunction "2_2") (pintype "passive"))
      (node (ref "J86") (pin "3") (pinfunction "3_3") (pintype "passive"))
      (node (ref "J86") (pin "4") (pinfunction "4_4") (pintype "passive"))
      (node (ref "J86") (pin "5") (pinfunction "5_5") (pintype "passive"))
    )
    (net (code "71") (name "Net-(U$1-C)") (class "Default")
      (node (ref "C2") (pin "+") (pinfunction "+_+") (pintype "passive"))
      (node (ref "U$1") (pin "1") (pinfunction "C_1") (pintype "passive"))
      (node (ref "U1") (pin "3") (pinfunction "IN_3") (pintype "input"))
    )
    (net (code "72") (name "Net-(U1-ADJ)") (class "Default")
      (node (ref "R2") (pin "1") (pinfunction "1_1") (pintype "passive"))
      (node (ref "R3") (pin "2") (pinfunction "2_2") (pintype "passive"))
      (node (ref "U1") (pin "1") (pinfunction "ADJ_1") (pintype "input"))
    )
    (net (code "73") (name "unconnected-(ATMEGA328P-ADC6-Pad19)") (class "Default")
      (node (ref "ATMEGA328P") (pin "19") (pinfunction "ADC6_19") (pintype "bidirectional"))
    )
    (net (code "74") (name "unconnected-(ATMEGA328P-ADC7-Pad22)") (class "Default")
      (node (ref "ATMEGA328P") (pin "22") (pinfunction "ADC7_22") (pintype "bidirectional"))
    )
    (net (code "75") (name "unconnected-(POWER-Pad8)") (class "Default")
      (node (ref "POWER") (pin "8") (pinfunction "8_8") (pintype "passive"))
    )
  )
)
